# LifterV02.net
KiCad netlist of a schematic drawn in EAGLE
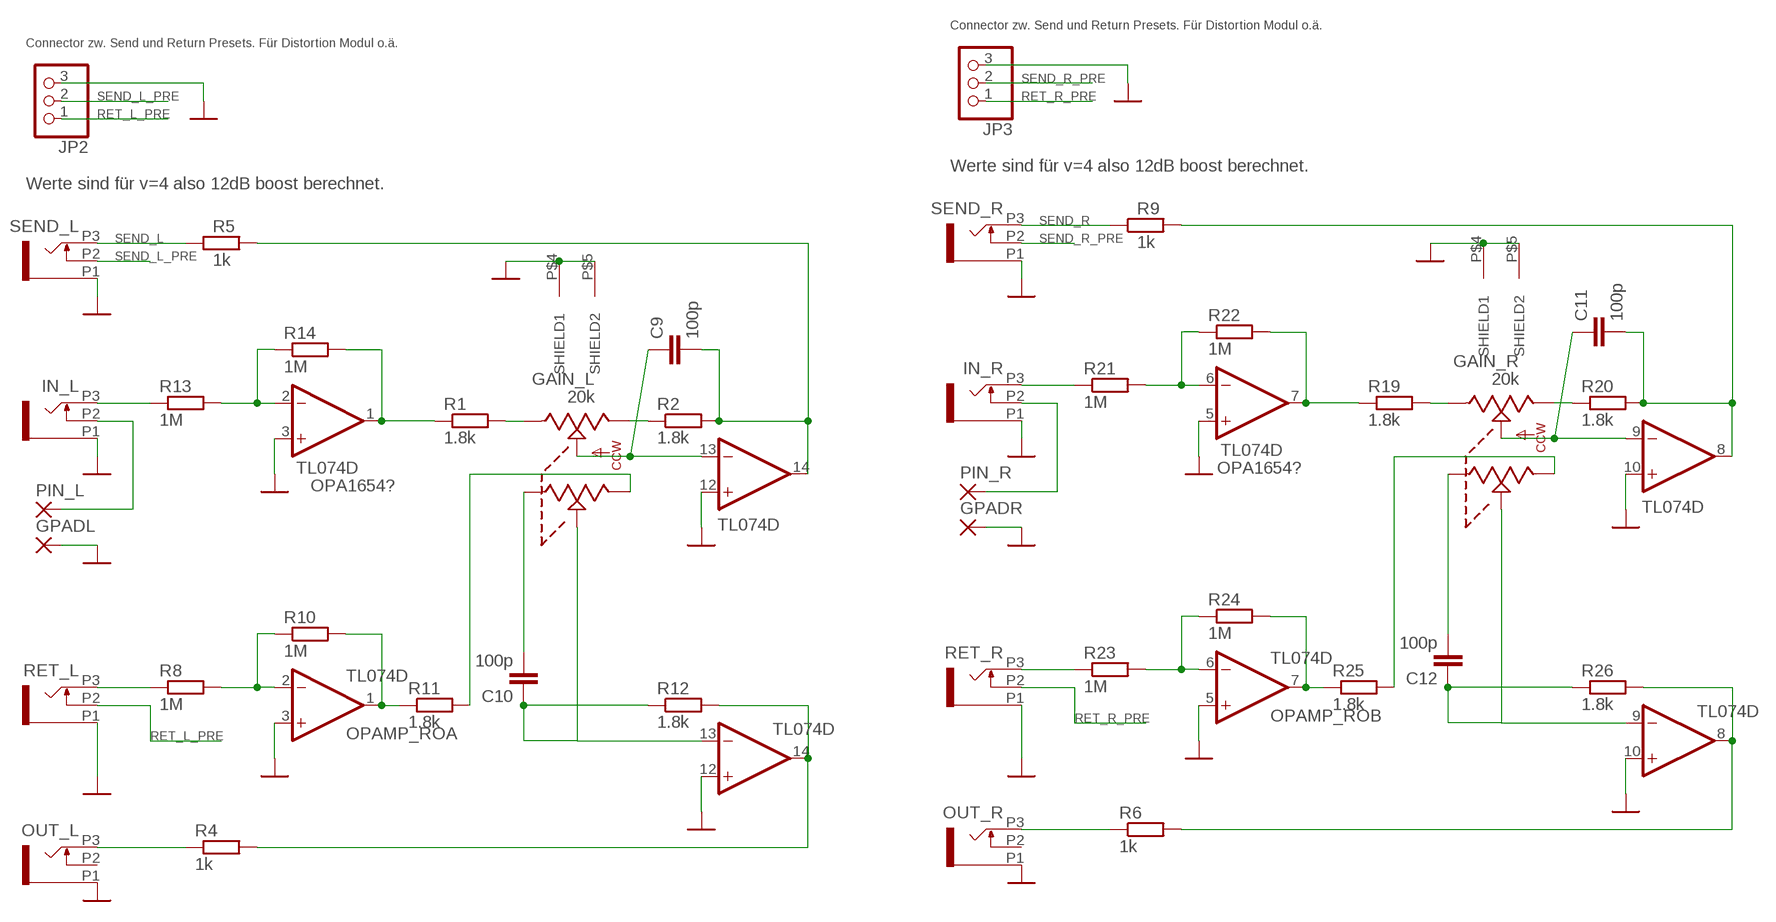
[diagram p0: schematic, sheet 1]
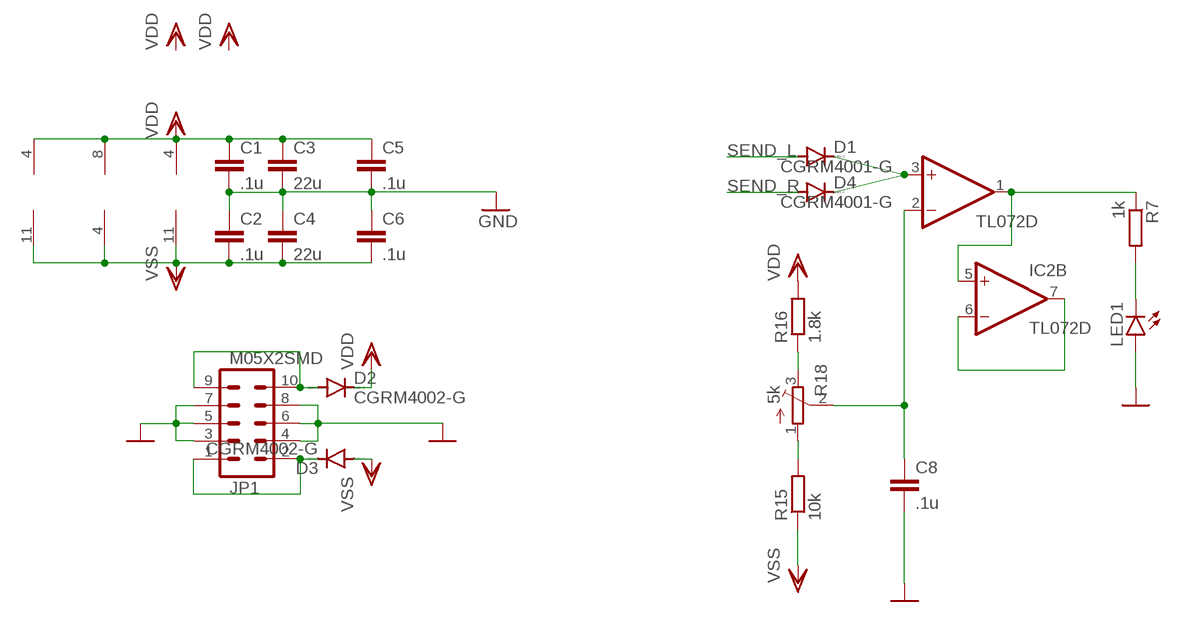
[diagram p1: schematic, sheet 2]

(export (version "E")
  (design (tool "Eeschema 10.0.6"))
  (components
    (comp (ref "C9")
      (value "100p")
      (footprint "eagle-import:C0603")
      (libsource (lib "eagle-import") (part "C-EUC0603"))
    )
    (comp (ref "C10")
      (value "100p")
      (footprint "eagle-import:C0603")
      (libsource (lib "eagle-import") (part "C-EUC0603"))
    )
    (comp (ref "C11")
      (value "100p")
      (footprint "eagle-import:C0603")
      (libsource (lib "eagle-import") (part "C-EUC0603"))
    )
    (comp (ref "C12")
      (value "100p")
      (footprint "eagle-import:C0603")
      (libsource (lib "eagle-import") (part "C-EUC0603"))
    )
    (comp (ref "GAIN_L")
      (value "20k")
      (footprint "eagle-import:TT_2TAP_VERTICAL")
      (libsource (lib "eagle-import") (part "POT_US_2X"))
    )
    (comp (ref "GAIN_R")
      (value "20k")
      (footprint "eagle-import:TT_2TAP_VERTICAL")
      (libsource (lib "eagle-import") (part "POT_US_2X"))
    )
    (comp (ref "GPADL")
      (value "3,17/1,3")
      (footprint "eagle-import:3,17_1,3")
      (libsource (lib "eagle-import") (part "3,17/1,3"))
    )
    (comp (ref "GPADR")
      (value "3,17/1,3")
      (footprint "eagle-import:3,17_1,3")
      (libsource (lib "eagle-import") (part "3,17/1,3"))
    )
    (comp (ref "IN_L")
      (value "PJ301_THONKICONN6")
      (footprint "eagle-import:WQP_PJ_301M6")
      (libsource (lib "eagle-import") (part "PJ301_THONKICONN6"))
    )
    (comp (ref "IN_R")
      (value "PJ301_THONKICONN6")
      (footprint "eagle-import:WQP_PJ_301M6")
      (libsource (lib "eagle-import") (part "PJ301_THONKICONN6"))
    )
    (comp (ref "JP2")
      (value "PINHD-1X3")
      (footprint "eagle-import:1X03")
      (libsource (lib "eagle-import") (part "PINHD-1X3"))
    )
    (comp (ref "JP3")
      (value "PINHD-1X3")
      (footprint "eagle-import:1X03")
      (libsource (lib "eagle-import") (part "PINHD-1X3"))
    )
    (comp (ref "OPAMP_IS")
      (value "TL074D")
      (footprint "eagle-import:SO14")
      (fields (field (name "SPICEPREFIX") "J"))
      (libsource (lib "eagle-import") (part "TL074D"))
    )
    (comp (ref "OPAMP_RO")
      (value "TL074D")
      (footprint "eagle-import:SO14")
      (fields (field (name "SPICEPREFIX") "J"))
      (libsource (lib "eagle-import") (part "TL074D"))
    )
    (comp (ref "OUT_L")
      (value "PJ301_THONKICONN6")
      (footprint "eagle-import:WQP_PJ_301M6")
      (libsource (lib "eagle-import") (part "PJ301_THONKICONN6"))
    )
    (comp (ref "OUT_R")
      (value "PJ301_THONKICONN6")
      (footprint "eagle-import:WQP_PJ_301M6")
      (libsource (lib "eagle-import") (part "PJ301_THONKICONN6"))
    )
    (comp (ref "PIN_L")
      (value "3,17/1,3")
      (footprint "eagle-import:3,17_1,3")
      (libsource (lib "eagle-import") (part "3,17/1,3"))
    )
    (comp (ref "PIN_R")
      (value "3,17/1,3")
      (footprint "eagle-import:3,17_1,3")
      (libsource (lib "eagle-import") (part "3,17/1,3"))
    )
    (comp (ref "R1")
      (value "1.8k")
      (footprint "eagle-import:R0603")
      (libsource (lib "eagle-import") (part "R-EU_R0603"))
    )
    (comp (ref "R2")
      (value "1.8k")
      (footprint "eagle-import:R0603")
      (libsource (lib "eagle-import") (part "R-EU_R0603"))
    )
    (comp (ref "R4")
      (value "1k")
      (footprint "eagle-import:R0603")
      (libsource (lib "eagle-import") (part "R-EU_R0603"))
    )
    (comp (ref "R5")
      (value "1k")
      (footprint "eagle-import:R0603")
      (libsource (lib "eagle-import") (part "R-EU_R0603"))
    )
    (comp (ref "R6")
      (value "1k")
      (footprint "eagle-import:R0603")
      (libsource (lib "eagle-import") (part "R-EU_R0603"))
    )
    (comp (ref "R8")
      (value "1M")
      (footprint "eagle-import:R0603")
      (libsource (lib "eagle-import") (part "R-EU_R0603"))
    )
    (comp (ref "R9")
      (value "1k")
      (footprint "eagle-import:R0603")
      (libsource (lib "eagle-import") (part "R-EU_R0603"))
    )
    (comp (ref "R10")
      (value "1M")
      (footprint "eagle-import:R0603")
      (libsource (lib "eagle-import") (part "R-EU_R0603"))
    )
    (comp (ref "R11")
      (value "1.8k")
      (footprint "eagle-import:R0603")
      (libsource (lib "eagle-import") (part "R-EU_R0603"))
    )
    (comp (ref "R12")
      (value "1.8k")
      (footprint "eagle-import:R0603")
      (libsource (lib "eagle-import") (part "R-EU_R0603"))
    )
    (comp (ref "R13")
      (value "1M")
      (footprint "eagle-import:R0603")
      (libsource (lib "eagle-import") (part "R-EU_R0603"))
    )
    (comp (ref "R14")
      (value "1M")
      (footprint "eagle-import:R0603")
      (libsource (lib "eagle-import") (part "R-EU_R0603"))
    )
    (comp (ref "R19")
      (value "1.8k")
      (footprint "eagle-import:R0603")
      (libsource (lib "eagle-import") (part "R-EU_R0603"))
    )
    (comp (ref "R20")
      (value "1.8k")
      (footprint "eagle-import:R0603")
      (libsource (lib "eagle-import") (part "R-EU_R0603"))
    )
    (comp (ref "R21")
      (value "1M")
      (footprint "eagle-import:R0603")
      (libsource (lib "eagle-import") (part "R-EU_R0603"))
    )
    (comp (ref "R22")
      (value "1M")
      (footprint "eagle-import:R0603")
      (libsource (lib "eagle-import") (part "R-EU_R0603"))
    )
    (comp (ref "R23")
      (value "1M")
      (footprint "eagle-import:R0603")
      (libsource (lib "eagle-import") (part "R-EU_R0603"))
    )
    (comp (ref "R24")
      (value "1M")
      (footprint "eagle-import:R0603")
      (libsource (lib "eagle-import") (part "R-EU_R0603"))
    )
    (comp (ref "R25")
      (value "1.8k")
      (footprint "eagle-import:R0603")
      (libsource (lib "eagle-import") (part "R-EU_R0603"))
    )
    (comp (ref "R26")
      (value "1.8k")
      (footprint "eagle-import:R0603")
      (libsource (lib "eagle-import") (part "R-EU_R0603"))
    )
    (comp (ref "RET_L")
      (value "PJ301_THONKICONN6")
      (footprint "eagle-import:WQP_PJ_301M6")
      (libsource (lib "eagle-import") (part "PJ301_THONKICONN6"))
    )
    (comp (ref "RET_R")
      (value "PJ301_THONKICONN6")
      (footprint "eagle-import:WQP_PJ_301M6")
      (libsource (lib "eagle-import") (part "PJ301_THONKICONN6"))
    )
    (comp (ref "SEND_L")
      (value "PJ301_THONKICONN6")
      (footprint "eagle-import:WQP_PJ_301M6")
      (libsource (lib "eagle-import") (part "PJ301_THONKICONN6"))
    )
    (comp (ref "SEND_R")
      (value "PJ301_THONKICONN6")
      (footprint "eagle-import:WQP_PJ_301M6")
      (libsource (lib "eagle-import") (part "PJ301_THONKICONN6"))
    )
    (comp (ref "C1")
      (value ".1u")
      (footprint "eagle-import:C0603")
      (libsource (lib "eagle-import") (part "C-EUC0603"))
    )
    (comp (ref "C2")
      (value ".1u")
      (footprint "eagle-import:C0603")
      (libsource (lib "eagle-import") (part "C-EUC0603"))
    )
    (comp (ref "C3")
      (value "22u")
      (footprint "eagle-import:C1210")
      (libsource (lib "eagle-import") (part "C-EUC1210"))
    )
    (comp (ref "C4")
      (value "22u")
      (footprint "eagle-import:C1210")
      (libsource (lib "eagle-import") (part "C-EUC1210"))
    )
    (comp (ref "C5")
      (value ".1u")
      (footprint "eagle-import:C0603")
      (libsource (lib "eagle-import") (part "C-EUC0603"))
    )
    (comp (ref "C6")
      (value ".1u")
      (footprint "eagle-import:C0603")
      (libsource (lib "eagle-import") (part "C-EUC0603"))
    )
    (comp (ref "C8")
      (value ".1u")
      (footprint "eagle-import:C0603")
      (libsource (lib "eagle-import") (part "C-EUC0603"))
    )
    (comp (ref "D1")
      (value "CGRM4001-G")
      (footprint "eagle-import:SOD-123_MINI-SMA")
      (libsource (lib "eagle-import") (part "CGRM400-G1"))
    )
    (comp (ref "D2")
      (value "CGRM4002-G")
      (footprint "eagle-import:SOD-123_MINI-SMA")
      (libsource (lib "eagle-import") (part "CGRM400-G2"))
    )
    (comp (ref "D3")
      (value "CGRM4002-G")
      (footprint "eagle-import:SOD-123_MINI-SMA")
      (libsource (lib "eagle-import") (part "CGRM400-G2"))
    )
    (comp (ref "D4")
      (value "CGRM4001-G")
      (footprint "eagle-import:SOD-123_MINI-SMA")
      (libsource (lib "eagle-import") (part "CGRM400-G1"))
    )
    (comp (ref "IC2")
      (value "TL072D")
      (footprint "eagle-import:SO08")
      (libsource (lib "eagle-import") (part "TL072D"))
    )
    (comp (ref "JP1")
      (value "M05X2SMD")
      (footprint "eagle-import:2X5-SMD")
      (libsource (lib "eagle-import") (part "M05X2SMD"))
    )
    (comp (ref "LED1")
      (value "LED3MM")
      (footprint "eagle-import:LED3MM")
      (libsource (lib "eagle-import") (part "LED3MM"))
    )
    (comp (ref "R7")
      (value "1k")
      (footprint "eagle-import:R0603")
      (libsource (lib "eagle-import") (part "R-EU_R0603"))
    )
    (comp (ref "R15")
      (value "10k")
      (footprint "eagle-import:R0603")
      (libsource (lib "eagle-import") (part "R-EU_R0603"))
    )
    (comp (ref "R16")
      (value "1.8k")
      (footprint "eagle-import:R0603")
      (libsource (lib "eagle-import") (part "R-EU_R0603"))
    )
    (comp (ref "R18")
      (value "5k")
      (footprint "eagle-import:3223G")
      (libsource (lib "eagle-import") (part "TRIM_EU-3223G"))
    )
  )
  (nets
    (net (code "1") (name "GND") (class "Default")
      (node (ref "C1") (pin "2") (pinfunction "2_2") (pintype "passive"))
      (node (ref "C2") (pin "1") (pinfunction "1_1") (pintype "passive"))
      (node (ref "C3") (pin "2") (pinfunction "2_2") (pintype "passive"))
      (node (ref "C4") (pin "1") (pinfunction "1_1") (pintype "passive"))
      (node (ref "C5") (pin "2") (pinfunction "2_2") (pintype "passive"))
      (node (ref "C6") (pin "1") (pinfunction "1_1") (pintype "passive"))
      (node (ref "C8") (pin "2") (pinfunction "2_2") (pintype "passive"))
      (node (ref "GAIN_L") (pin "P$4") (pinfunction "SHIELD1_P$4") (pintype "bidirectional"))
      (node (ref "GAIN_L") (pin "P$5") (pinfunction "SHIELD2_P$5") (pintype "bidirectional"))
      (node (ref "GAIN_R") (pin "P$4") (pinfunction "SHIELD1_P$4") (pintype "bidirectional"))
      (node (ref "GAIN_R") (pin "P$5") (pinfunction "SHIELD2_P$5") (pintype "bidirectional"))
      (node (ref "GPADL") (pin "1") (pinfunction "P_1") (pintype "passive"))
      (node (ref "GPADR") (pin "1") (pinfunction "P_1") (pintype "passive"))
      (node (ref "IN_L") (pin "P1") (pinfunction "1_P1") (pintype "passive"))
      (node (ref "IN_R") (pin "P1") (pinfunction "1_P1") (pintype "passive"))
      (node (ref "JP1") (pin "3") (pinfunction "3_3") (pintype "passive"))
      (node (ref "JP1") (pin "4") (pinfunction "4_4") (pintype "passive"))
      (node (ref "JP1") (pin "5") (pinfunction "5_5") (pintype "passive"))
      (node (ref "JP1") (pin "6") (pinfunction "6_6") (pintype "passive"))
      (node (ref "JP1") (pin "7") (pinfunction "7_7") (pintype "passive"))
      (node (ref "JP1") (pin "8") (pinfunction "8_8") (pintype "passive"))
      (node (ref "JP2") (pin "3") (pinfunction "3_3") (pintype "passive"))
      (node (ref "JP3") (pin "3") (pinfunction "3_3") (pintype "passive"))
      (node (ref "LED1") (pin "A") (pinfunction "A_A") (pintype "passive"))
      (node (ref "OPAMP_IS") (pin "10") (pinfunction "+IN_10") (pintype "input"))
      (node (ref "OPAMP_IS") (pin "12") (pinfunction "+IN_12") (pintype "input"))
      (node (ref "OPAMP_IS") (pin "3") (pinfunction "+IN_3") (pintype "input"))
      (node (ref "OPAMP_IS") (pin "5") (pinfunction "+IN_5") (pintype "input"))
      (node (ref "OPAMP_RO") (pin "10") (pinfunction "+IN_10") (pintype "input"))
      (node (ref "OPAMP_RO") (pin "12") (pinfunction "+IN_12") (pintype "input"))
      (node (ref "OPAMP_RO") (pin "3") (pinfunction "+IN_3") (pintype "input"))
      (node (ref "OPAMP_RO") (pin "5") (pinfunction "+IN_5") (pintype "input"))
      (node (ref "OUT_L") (pin "P1") (pinfunction "1_P1") (pintype "passive"))
      (node (ref "OUT_R") (pin "P1") (pinfunction "1_P1") (pintype "passive"))
      (node (ref "RET_L") (pin "P1") (pinfunction "1_P1") (pintype "passive"))
      (node (ref "RET_R") (pin "P1") (pinfunction "1_P1") (pintype "passive"))
      (node (ref "SEND_L") (pin "P1") (pinfunction "1_P1") (pintype "passive"))
      (node (ref "SEND_R") (pin "P1") (pinfunction "1_P1") (pintype "passive"))
    )
    (net (code "2") (name "Net-(C10-Pad2)") (class "Default")
      (node (ref "C10") (pin "2") (pinfunction "2_2") (pintype "passive"))
      (node (ref "GAIN_L") (pin "CW1") (pinfunction "CW1_CW1") (pintype "passive"))
    )
    (net (code "3") (name "Net-(C12-Pad2)") (class "Default")
      (node (ref "C12") (pin "2") (pinfunction "2_2") (pintype "passive"))
      (node (ref "GAIN_R") (pin "CW1") (pinfunction "CW1_CW1") (pintype "passive"))
    )
    (net (code "4") (name "Net-(D2-PadA)") (class "Default")
      (node (ref "D2") (pin "A") (pinfunction "A_A") (pintype "passive"))
      (node (ref "JP1") (pin "10") (pinfunction "10_10") (pintype "passive"))
      (node (ref "JP1") (pin "9") (pinfunction "9_9") (pintype "passive"))
    )
    (net (code "5") (name "Net-(D3-PadC)") (class "Default")
      (node (ref "D3") (pin "C") (pinfunction "C_C") (pintype "passive"))
      (node (ref "JP1") (pin "1") (pinfunction "1_1") (pintype "passive"))
      (node (ref "JP1") (pin "2") (pinfunction "2_2") (pintype "passive"))
    )
    (net (code "6") (name "Net-(GAIN_L-PadCCW)") (class "Default")
      (node (ref "GAIN_L") (pin "CCW") (pinfunction "CCW_CCW") (pintype "passive"))
      (node (ref "R2") (pin "1") (pinfunction "1_1") (pintype "passive"))
    )
    (net (code "7") (name "Net-(GAIN_L-PadCCW1)") (class "Default")
      (node (ref "GAIN_L") (pin "CCW1") (pinfunction "CCW1_CCW1") (pintype "passive"))
      (node (ref "R11") (pin "2") (pinfunction "2_2") (pintype "passive"))
    )
    (net (code "8") (name "Net-(GAIN_L-PadCW)") (class "Default")
      (node (ref "GAIN_L") (pin "CW") (pinfunction "CW_CW") (pintype "passive"))
      (node (ref "R1") (pin "2") (pinfunction "2_2") (pintype "passive"))
    )
    (net (code "9") (name "Net-(GAIN_R-PadCCW)") (class "Default")
      (node (ref "GAIN_R") (pin "CCW") (pinfunction "CCW_CCW") (pintype "passive"))
      (node (ref "R20") (pin "1") (pinfunction "1_1") (pintype "passive"))
    )
    (net (code "10") (name "Net-(GAIN_R-PadCCW1)") (class "Default")
      (node (ref "GAIN_R") (pin "CCW1") (pinfunction "CCW1_CCW1") (pintype "passive"))
      (node (ref "R25") (pin "2") (pinfunction "2_2") (pintype "passive"))
    )
    (net (code "11") (name "Net-(GAIN_R-PadCW)") (class "Default")
      (node (ref "GAIN_R") (pin "CW") (pinfunction "CW_CW") (pintype "passive"))
      (node (ref "R19") (pin "2") (pinfunction "2_2") (pintype "passive"))
    )
    (net (code "12") (name "Net-(IC2A-+IN)") (class "Default")
      (node (ref "D1") (pin "C") (pinfunction "C_C") (pintype "passive"))
      (node (ref "D4") (pin "C") (pinfunction "C_C") (pintype "passive"))
      (node (ref "IC2") (pin "3") (pinfunction "+IN_3") (pintype "input"))
    )
    (net (code "13") (name "Net-(IC2A--IN)") (class "Default")
      (node (ref "C8") (pin "1") (pinfunction "1_1") (pintype "passive"))
      (node (ref "IC2") (pin "2") (pinfunction "-IN_2") (pintype "input"))
      (node (ref "R18") (pin "2") (pinfunction "S_2") (pintype "passive"))
    )
    (net (code "14") (name "Net-(IC2A-OUT)") (class "Default")
      (node (ref "IC2") (pin "1") (pinfunction "OUT_1") (pintype "output"))
      (node (ref "IC2") (pin "5") (pinfunction "+IN_5") (pintype "input"))
      (node (ref "R7") (pin "1") (pinfunction "1_1") (pintype "passive"))
    )
    (net (code "15") (name "Net-(IC2B--IN)") (class "Default")
      (node (ref "IC2") (pin "6") (pinfunction "-IN_6") (pintype "input"))
      (node (ref "IC2") (pin "7") (pinfunction "OUT_7") (pintype "output"))
    )
    (net (code "16") (name "Net-(IN_L-2)") (class "Default")
      (node (ref "IN_L") (pin "P2") (pinfunction "2_P2") (pintype "passive"))
      (node (ref "PIN_L") (pin "1") (pinfunction "P_1") (pintype "passive"))
    )
    (net (code "17") (name "Net-(IN_L-3)") (class "Default")
      (node (ref "IN_L") (pin "P3") (pinfunction "3_P3") (pintype "passive"))
      (node (ref "R13") (pin "1") (pinfunction "1_1") (pintype "passive"))
    )
    (net (code "18") (name "Net-(IN_R-2)") (class "Default")
      (node (ref "IN_R") (pin "P2") (pinfunction "2_P2") (pintype "passive"))
      (node (ref "PIN_R") (pin "1") (pinfunction "P_1") (pintype "passive"))
    )
    (net (code "19") (name "Net-(IN_R-3)") (class "Default")
      (node (ref "IN_R") (pin "P3") (pinfunction "3_P3") (pintype "passive"))
      (node (ref "R21") (pin "1") (pinfunction "1_1") (pintype "passive"))
    )
    (net (code "20") (name "Net-(LED1-C)") (class "Default")
      (node (ref "LED1") (pin "K") (pinfunction "C_K") (pintype "passive"))
      (node (ref "R7") (pin "2") (pinfunction "2_2") (pintype "passive"))
    )
    (net (code "21") (name "Net-(OPAMP_ISA--IN)") (class "Default")
      (node (ref "OPAMP_IS") (pin "2") (pinfunction "-IN_2") (pintype "input"))
      (node (ref "R13") (pin "2") (pinfunction "2_2") (pintype "passive"))
      (node (ref "R14") (pin "1") (pinfunction "1_1") (pintype "passive"))
    )
    (net (code "22") (name "Net-(OPAMP_ISA-OUT)") (class "Default")
      (node (ref "OPAMP_IS") (pin "1") (pinfunction "OUT_1") (pintype "output"))
      (node (ref "R1") (pin "1") (pinfunction "1_1") (pintype "passive"))
      (node (ref "R14") (pin "2") (pinfunction "2_2") (pintype "passive"))
    )
    (net (code "23") (name "Net-(OPAMP_ISB--IN)") (class "Default")
      (node (ref "OPAMP_IS") (pin "6") (pinfunction "-IN_6") (pintype "input"))
      (node (ref "R21") (pin "2") (pinfunction "2_2") (pintype "passive"))
      (node (ref "R22") (pin "1") (pinfunction "1_1") (pintype "passive"))
    )
    (net (code "24") (name "Net-(OPAMP_ISB-OUT)") (class "Default")
      (node (ref "OPAMP_IS") (pin "7") (pinfunction "OUT_7") (pintype "output"))
      (node (ref "R19") (pin "1") (pinfunction "1_1") (pintype "passive"))
      (node (ref "R22") (pin "2") (pinfunction "2_2") (pintype "passive"))
    )
    (net (code "25") (name "Net-(OPAMP_ISC--IN)") (class "Default")
      (node (ref "C11") (pin "1") (pinfunction "1_1") (pintype "passive"))
      (node (ref "GAIN_R") (pin "CENTER") (pinfunction "CENTER_CENTER") (pintype "passive"))
      (node (ref "OPAMP_IS") (pin "9") (pinfunction "-IN_9") (pintype "input"))
    )
    (net (code "26") (name "Net-(OPAMP_ISC-OUT)") (class "Default")
      (node (ref "C11") (pin "2") (pinfunction "2_2") (pintype "passive"))
      (node (ref "OPAMP_IS") (pin "8") (pinfunction "OUT_8") (pintype "output"))
      (node (ref "R20") (pin "2") (pinfunction "2_2") (pintype "passive"))
      (node (ref "R9") (pin "2") (pinfunction "2_2") (pintype "passive"))
    )
    (net (code "27") (name "Net-(OPAMP_ISD--IN)") (class "Default")
      (node (ref "C9") (pin "1") (pinfunction "1_1") (pintype "passive"))
      (node (ref "GAIN_L") (pin "CENTER") (pinfunction "CENTER_CENTER") (pintype "passive"))
      (node (ref "OPAMP_IS") (pin "13") (pinfunction "-IN_13") (pintype "input"))
    )
    (net (code "28") (name "Net-(OPAMP_ISD-OUT)") (class "Default")
      (node (ref "C9") (pin "2") (pinfunction "2_2") (pintype "passive"))
      (node (ref "OPAMP_IS") (pin "14") (pinfunction "OUT_14") (pintype "output"))
      (node (ref "R2") (pin "2") (pinfunction "2_2") (pintype "passive"))
      (node (ref "R5") (pin "2") (pinfunction "2_2") (pintype "passive"))
    )
    (net (code "29") (name "Net-(OPAMP_ROA--IN)") (class "Default")
      (node (ref "OPAMP_RO") (pin "2") (pinfunction "-IN_2") (pintype "input"))
      (node (ref "R10") (pin "1") (pinfunction "1_1") (pintype "passive"))
      (node (ref "R8") (pin "2") (pinfunction "2_2") (pintype "passive"))
    )
    (net (code "30") (name "Net-(OPAMP_ROA-OUT)") (class "Default")
      (node (ref "OPAMP_RO") (pin "1") (pinfunction "OUT_1") (pintype "output"))
      (node (ref "R10") (pin "2") (pinfunction "2_2") (pintype "passive"))
      (node (ref "R11") (pin "1") (pinfunction "1_1") (pintype "passive"))
    )
    (net (code "31") (name "Net-(OPAMP_ROB--IN)") (class "Default")
      (node (ref "OPAMP_RO") (pin "6") (pinfunction "-IN_6") (pintype "input"))
      (node (ref "R23") (pin "2") (pinfunction "2_2") (pintype "passive"))
      (node (ref "R24") (pin "1") (pinfunction "1_1") (pintype "passive"))
    )
    (net (code "32") (name "Net-(OPAMP_ROB-OUT)") (class "Default")
      (node (ref "OPAMP_RO") (pin "7") (pinfunction "OUT_7") (pintype "output"))
      (node (ref "R24") (pin "2") (pinfunction "2_2") (pintype "passive"))
      (node (ref "R25") (pin "1") (pinfunction "1_1") (pintype "passive"))
    )
    (net (code "33") (name "Net-(OPAMP_ROC--IN)") (class "Default")
      (node (ref "C12") (pin "1") (pinfunction "1_1") (pintype "passive"))
      (node (ref "GAIN_R") (pin "CENTER1") (pinfunction "CENTER1_CENTER1") (pintype "passive"))
      (node (ref "OPAMP_RO") (pin "9") (pinfunction "-IN_9") (pintype "input"))
      (node (ref "R26") (pin "1") (pinfunction "1_1") (pintype "passive"))
    )
    (net (code "34") (name "Net-(OPAMP_ROC-OUT)") (class "Default")
      (node (ref "OPAMP_RO") (pin "8") (pinfunction "OUT_8") (pintype "output"))
      (node (ref "R26") (pin "2") (pinfunction "2_2") (pintype "passive"))
      (node (ref "R6") (pin "2") (pinfunction "2_2") (pintype "passive"))
    )
    (net (code "35") (name "Net-(OPAMP_ROD--IN)") (class "Default")
      (node (ref "C10") (pin "1") (pinfunction "1_1") (pintype "passive"))
      (node (ref "GAIN_L") (pin "CENTER1") (pinfunction "CENTER1_CENTER1") (pintype "passive"))
      (node (ref "OPAMP_RO") (pin "13") (pinfunction "-IN_13") (pintype "input"))
      (node (ref "R12") (pin "1") (pinfunction "1_1") (pintype "passive"))
    )
    (net (code "36") (name "Net-(OPAMP_ROD-OUT)") (class "Default")
      (node (ref "OPAMP_RO") (pin "14") (pinfunction "OUT_14") (pintype "output"))
      (node (ref "R12") (pin "2") (pinfunction "2_2") (pintype "passive"))
      (node (ref "R4") (pin "2") (pinfunction "2_2") (pintype "passive"))
    )
    (net (code "37") (name "Net-(OUT_L-3)") (class "Default")
      (node (ref "OUT_L") (pin "P3") (pinfunction "3_P3") (pintype "passive"))
      (node (ref "R4") (pin "1") (pinfunction "1_1") (pintype "passive"))
    )
    (net (code "38") (name "Net-(OUT_R-3)") (class "Default")
      (node (ref "OUT_R") (pin "P3") (pinfunction "3_P3") (pintype "passive"))
      (node (ref "R6") (pin "1") (pinfunction "1_1") (pintype "passive"))
    )
    (net (code "39") (name "Net-(R18-A)") (class "Default")
      (node (ref "R15") (pin "2") (pinfunction "2_2") (pintype "passive"))
      (node (ref "R18") (pin "1") (pinfunction "A_1") (pintype "passive"))
    )
    (net (code "40") (name "Net-(R18-E)") (class "Default")
      (node (ref "R16") (pin "1") (pinfunction "1_1") (pintype "passive"))
      (node (ref "R18") (pin "3") (pinfunction "E_3") (pintype "passive"))
    )
    (net (code "41") (name "Net-(RET_L-3)") (class "Default")
      (node (ref "R8") (pin "1") (pinfunction "1_1") (pintype "passive"))
      (node (ref "RET_L") (pin "P3") (pinfunction "3_P3") (pintype "passive"))
    )
    (net (code "42") (name "Net-(RET_R-3)") (class "Default")
      (node (ref "R23") (pin "1") (pinfunction "1_1") (pintype "passive"))
      (node (ref "RET_R") (pin "P3") (pinfunction "3_P3") (pintype "passive"))
    )
    (net (code "43") (name "RET_L_PRE") (class "Default")
      (node (ref "JP2") (pin "1") (pinfunction "1_1") (pintype "passive"))
      (node (ref "RET_L") (pin "P2") (pinfunction "2_P2") (pintype "passive"))
    )
    (net (code "44") (name "RET_R_PRE") (class "Default")
      (node (ref "JP3") (pin "1") (pinfunction "1_1") (pintype "passive"))
      (node (ref "RET_R") (pin "P2") (pinfunction "2_P2") (pintype "passive"))
    )
    (net (code "45") (name "SEND_L") (class "Default")
      (node (ref "D1") (pin "A") (pinfunction "A_A") (pintype "passive"))
      (node (ref "R5") (pin "1") (pinfunction "1_1") (pintype "passive"))
      (node (ref "SEND_L") (pin "P3") (pinfunction "3_P3") (pintype "passive"))
    )
    (net (code "46") (name "SEND_L_PRE") (class "Default")
      (node (ref "JP2") (pin "2") (pinfunction "2_2") (pintype "passive"))
      (node (ref "SEND_L") (pin "P2") (pinfunction "2_P2") (pintype "passive"))
    )
    (net (code "47") (name "SEND_R") (class "Default")
      (node (ref "D4") (pin "A") (pinfunction "A_A") (pintype "passive"))
      (node (ref "R9") (pin "1") (pinfunction "1_1") (pintype "passive"))
      (node (ref "SEND_R") (pin "P3") (pinfunction "3_P3") (pintype "passive"))
    )
    (net (code "48") (name "SEND_R_PRE") (class "Default")
      (node (ref "JP3") (pin "2") (pinfunction "2_2") (pintype "passive"))
      (node (ref "SEND_R") (pin "P2") (pinfunction "2_P2") (pintype "passive"))
    )
    (net (code "49") (name "VDD") (class "Default")
      (node (ref "C1") (pin "1") (pinfunction "1_1") (pintype "passive"))
      (node (ref "C3") (pin "1") (pinfunction "1_1") (pintype "passive"))
      (node (ref "C5") (pin "1") (pinfunction "1_1") (pintype "passive"))
      (node (ref "D2") (pin "C") (pinfunction "C_C") (pintype "passive"))
      (node (ref "IC2") (pin "8") (pinfunction "V+_8") (pintype "power_in"))
      (node (ref "OPAMP_IS") (pin "4") (pinfunction "V+_4") (pintype "power_in"))
      (node (ref "OPAMP_RO") (pin "4") (pinfunction "V+_4") (pintype "power_in"))
      (node (ref "R16") (pin "2") (pinfunction "2_2") (pintype "passive"))
    )
    (net (code "50") (name "VSS") (class "Default")
      (node (ref "C2") (pin "2") (pinfunction "2_2") (pintype "passive"))
      (node (ref "C4") (pin "2") (pinfunction "2_2") (pintype "passive"))
      (node (ref "C6") (pin "2") (pinfunction "2_2") (pintype "passive"))
      (node (ref "D3") (pin "A") (pinfunction "A_A") (pintype "passive"))
      (node (ref "IC2") (pin "4") (pinfunction "V-_4") (pintype "power_in"))
      (node (ref "OPAMP_IS") (pin "11") (pinfunction "V-_11") (pintype "power_in"))
      (node (ref "OPAMP_RO") (pin "11") (pinfunction "V-_11") (pintype "power_in"))
      (node (ref "R15") (pin "1") (pinfunction "1_1") (pintype "passive"))
    )
    (net (code "51") (name "unconnected-(OUT_L-2-PadP2)") (class "Default")
      (node (ref "OUT_L") (pin "P2") (pinfunction "2_P2") (pintype "passive"))
    )
    (net (code "52") (name "unconnected-(OUT_R-2-PadP2)") (class "Default")
      (node (ref "OUT_R") (pin "P2") (pinfunction "2_P2") (pintype "passive"))
    )
  )
)
